# SBT10X_single_led.net
KiCad netlist of a schematic drawn in EasyEDA Pro
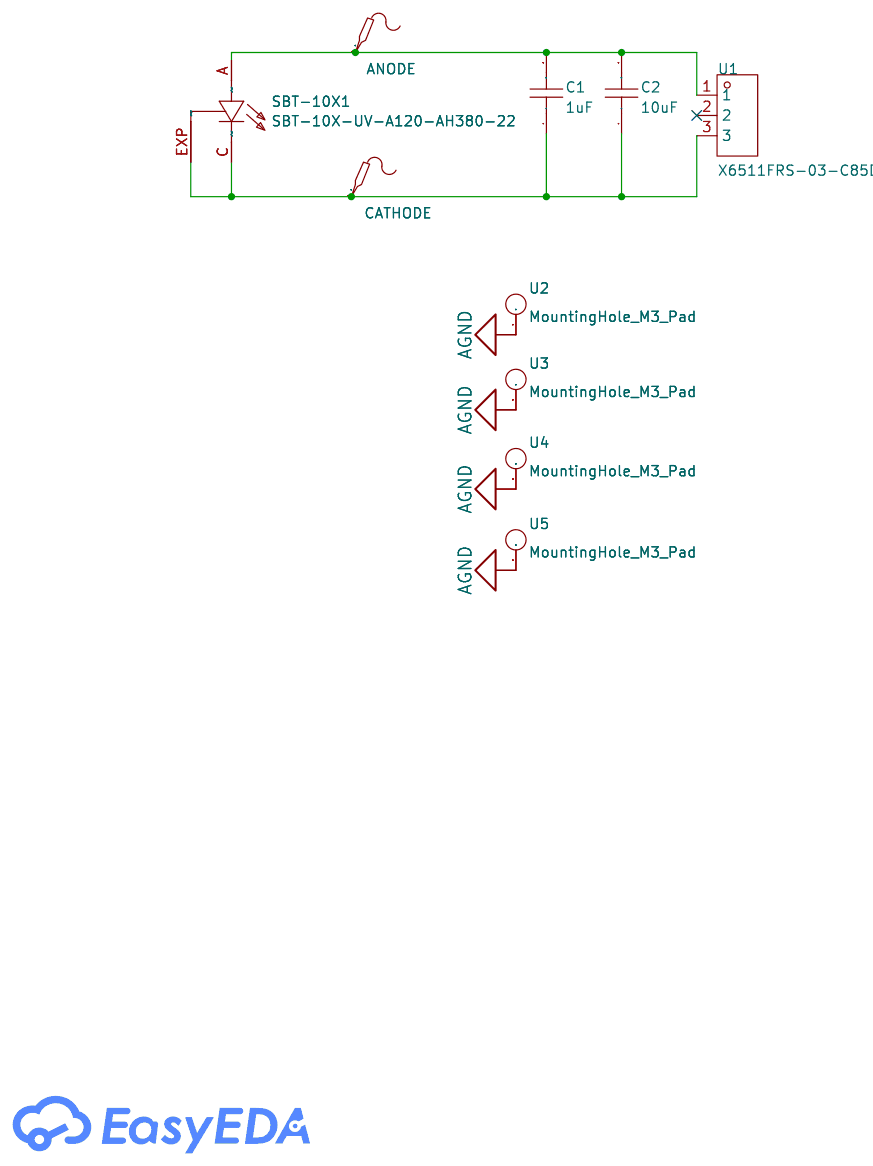
[diagram p0: schematic sheet]

(export (version "E")
  (design (tool "Eeschema 10.0.6"))
  (components
    (comp (ref "ANODE")
      (value "~")
      (footprint "easyedapro:Test-Point-0.5mm")
      (description "Test Point 测试点")
      (libsource (lib "easyedapro") (part "Test-Point"))
    )
    (comp (ref "C1")
      (value "1uF")
      (footprint "easyedapro:C0805")
      (description "Capacitance:1uF Tolerance:±10% Tolerance:±10% Voltage Rating:50V Temperature Coefficient:X7R")
      (fields (field (name "Manufacturer Part") "08055C105KAT2A") (field (name "Manufacturer") "Kyocera AVX"))
      (libsource (lib "easyedapro") (part "08055C105KAT2A"))
    )
    (comp (ref "C2")
      (value "10uF")
      (footprint "easyedapro:C1206")
      (description "Capacitance:10uF Tolerance:±10% Tolerance:±10% Voltage Rating:50V Temperature Coefficient:X7R")
      (fields
        (field (name "Manufacturer Part") "CGA1206X7R106K500NT")
        (field (name "Manufacturer") "HRE(芯声)")
      )
      (libsource (lib "easyedapro") (part "CGA1206X7R106K500NT"))
    )
    (comp (ref "CATHODE")
      (value "~")
      (footprint "easyedapro:Test-Point-0.5mm")
      (description "Test Point 测试点")
      (libsource (lib "easyedapro") (part "Test-Point"))
    )
    (comp (ref "SBT-10X1")
      (value "SBT-10X-UV-A120-AH380-22")
      (footprint "easyedapro:custom_lib:LED_SBT-10X-UV-A120-AH380-22")
      (fields (field (name "MANUFACTURER") "Luminus Devices"))
      (libsource (lib "easyedapro") (part "SBT-10X-UV-A120-AH380-22_SBT-10X-UV-A120-AH380-22"))
    )
    (comp (ref "U1")
      (value "X6511FRS-03-C85D30")
      (footprint "easyedapro:HDR-SMD_3P-P2.54-H-F-L11.5")
      (fields (field (name "Manufacturer") "XKB Connectivity(中国星坤)"))
      (libsource (lib "easyedapro") (part "X6511FRS-03-C85D30"))
    )
    (comp (ref "U2")
      (value "MountingHole_M3_Pad")
      (footprint "easyedapro:MountingHole_3.2mm_M3_DIN965_Pad_TopOnly")
      (libsource (lib "easyedapro") (part "Mounting_M3_Hole_Pad"))
    )
    (comp (ref "U3")
      (value "MountingHole_M3_Pad")
      (footprint "easyedapro:MountingHole_3.2mm_M3_DIN965_Pad_TopOnly")
      (libsource (lib "easyedapro") (part "Mounting_M3_Hole_Pad"))
    )
    (comp (ref "U4")
      (value "MountingHole_M3_Pad")
      (footprint "easyedapro:MountingHole_3.2mm_M3_DIN965_Pad_TopOnly")
      (libsource (lib "easyedapro") (part "Mounting_M3_Hole_Pad"))
    )
    (comp (ref "U5")
      (value "MountingHole_M3_Pad")
      (footprint "easyedapro:MountingHole_3.2mm_M3_DIN965_Pad_TopOnly")
      (libsource (lib "easyedapro") (part "Mounting_M3_Hole_Pad"))
    )
  )
  (nets
    (net (code "1") (name "AGND") (class "Default")
      (node (ref "U2") (pin "1") (pinfunction "1_1") (pintype "input"))
      (node (ref "U3") (pin "1") (pinfunction "1_1") (pintype "input"))
      (node (ref "U4") (pin "1") (pinfunction "1_1") (pintype "input"))
      (node (ref "U5") (pin "1") (pinfunction "1_1") (pintype "input"))
    )
    (net (code "2") (name "Net-(ANODE-Pad1)") (class "Default")
      (node (ref "ANODE") (pin "1") (pinfunction "1_1") (pintype "unspecified"))
      (node (ref "C1") (pin "2") (pinfunction "2_2") (pintype "unspecified"))
      (node (ref "C2") (pin "2") (pinfunction "2_2") (pintype "unspecified"))
      (node (ref "SBT-10X1") (pin "A") (pinfunction "~_A") (pintype "unspecified"))
      (node (ref "U1") (pin "1") (pinfunction "1_1") (pintype "unspecified"))
    )
    (net (code "3") (name "Net-(C1-Pad1)") (class "Default")
      (node (ref "C1") (pin "1") (pinfunction "1_1") (pintype "unspecified"))
      (node (ref "C2") (pin "1") (pinfunction "1_1") (pintype "unspecified"))
      (node (ref "CATHODE") (pin "1") (pinfunction "1_1") (pintype "unspecified"))
      (node (ref "SBT-10X1") (pin "C") (pinfunction "~_C") (pintype "unspecified"))
      (node (ref "SBT-10X1") (pin "EXP") (pinfunction "~_EXP") (pintype "unspecified"))
      (node (ref "U1") (pin "3") (pinfunction "3_3") (pintype "unspecified"))
    )
    (net (code "4") (name "unconnected-(U1-Pad2)") (class "Default")
      (node (ref "U1") (pin "2") (pinfunction "2_2") (pintype "unspecified+no_connect"))
    )
  )
)
